# master-board_plus_slave.net
KiCad netlist of a schematic drawn in EAGLE
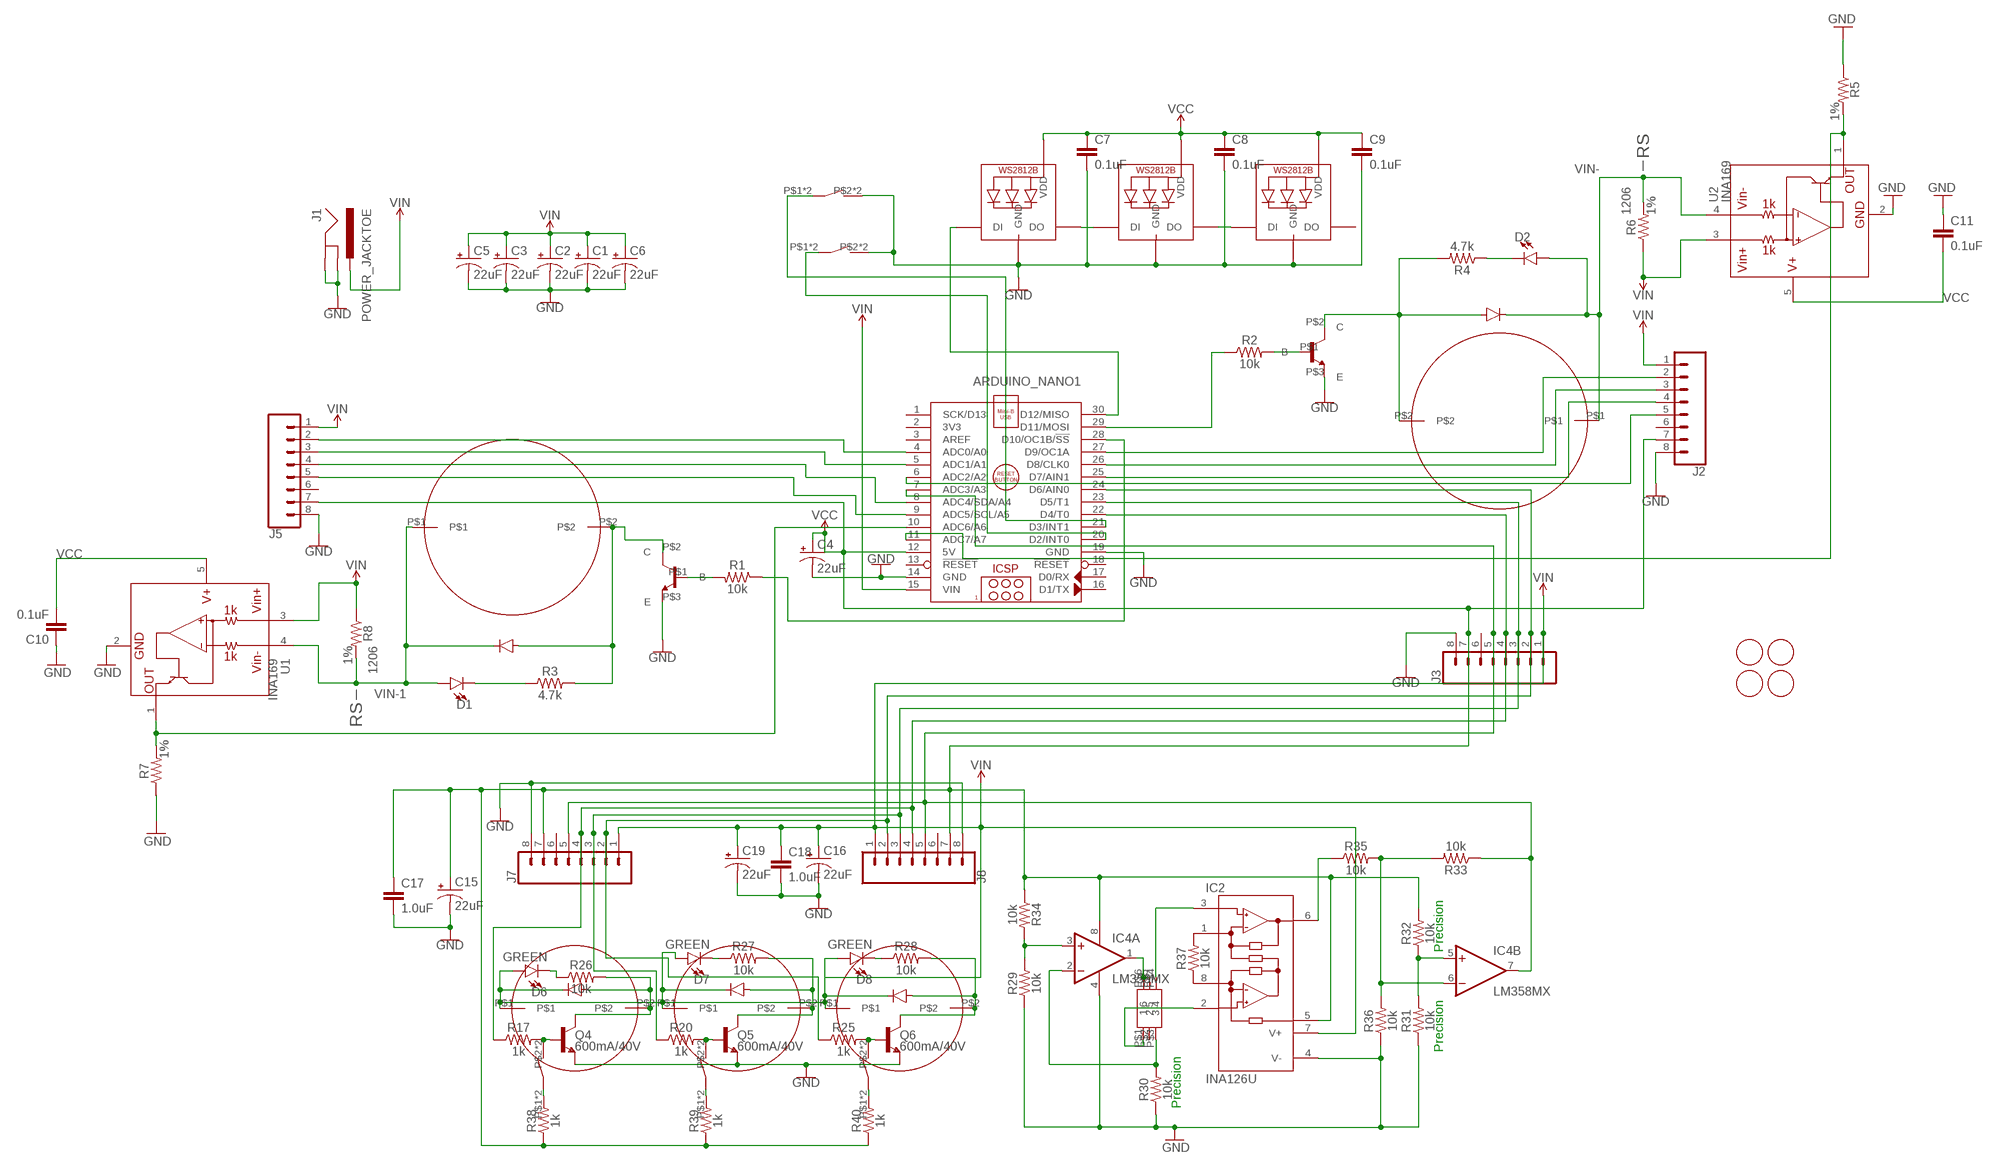
[diagram p0: schematic, sheet 1]

(export (version "E")
  (design (tool "Eeschema 10.0.6"))
  (components
    (comp (ref "ARDUINO_NANO1")
      (value "ARDUINO_NANO")
      (footprint "eagle-import:ARDUINO_NANO")
      (libsource (lib "eagle-import") (part "ARDUINO_NANO"))
    )
    (comp (ref "C1")
      (value "22uF")
      (footprint "eagle-import:PANASONIC_C")
      (libsource (lib "eagle-import") (part "22UF-POLAR-PANASONIC_C-35V-20%"))
    )
    (comp (ref "C2")
      (value "22uF")
      (footprint "eagle-import:PANASONIC_C")
      (libsource (lib "eagle-import") (part "22UF-POLAR-PANASONIC_C-35V-20%"))
    )
    (comp (ref "C3")
      (value "22uF")
      (footprint "eagle-import:PANASONIC_C")
      (libsource (lib "eagle-import") (part "22UF-POLAR-PANASONIC_C-35V-20%"))
    )
    (comp (ref "C4")
      (value "22uF")
      (footprint "eagle-import:PANASONIC_C")
      (libsource (lib "eagle-import") (part "22UF-POLAR-PANASONIC_C-35V-20%"))
    )
    (comp (ref "C5")
      (value "22uF")
      (footprint "eagle-import:PANASONIC_C")
      (libsource (lib "eagle-import") (part "22UF-POLAR-PANASONIC_C-35V-20%"))
    )
    (comp (ref "C6")
      (value "22uF")
      (footprint "eagle-import:PANASONIC_C")
      (libsource (lib "eagle-import") (part "22UF-POLAR-PANASONIC_C-35V-20%"))
    )
    (comp (ref "C7")
      (value "0.1uF")
      (footprint "eagle-import:0603")
      (libsource (lib "eagle-import") (part "0.1UF-0603-25V-(+80/-20%)"))
    )
    (comp (ref "C8")
      (value "0.1uF")
      (footprint "eagle-import:0603")
      (libsource (lib "eagle-import") (part "0.1UF-0603-25V-(+80/-20%)"))
    )
    (comp (ref "C9")
      (value "0.1uF")
      (footprint "eagle-import:0603")
      (libsource (lib "eagle-import") (part "0.1UF-0603-25V-(+80/-20%)"))
    )
    (comp (ref "C10")
      (value "0.1uF")
      (footprint "eagle-import:0603-CAP")
      (libsource (lib "eagle-import") (part "CAP0603-CAP"))
    )
    (comp (ref "C11")
      (value "0.1uF")
      (footprint "eagle-import:0603-CAP")
      (libsource (lib "eagle-import") (part "CAP0603-CAP"))
    )
    (comp (ref "C15")
      (value "22uF")
      (footprint "eagle-import:PANASONIC_C")
      (libsource (lib "eagle-import") (part "22UF-POLAR-PANASONIC_C-35V-20%"))
    )
    (comp (ref "C16")
      (value "22uF")
      (footprint "eagle-import:PANASONIC_C")
      (libsource (lib "eagle-import") (part "22UF-POLAR-PANASONIC_C-35V-20%"))
    )
    (comp (ref "C17")
      (value "1.0uF")
      (footprint "eagle-import:0603")
      (libsource (lib "eagle-import") (part "1.0UF-0603-16V-10%"))
    )
    (comp (ref "C18")
      (value "1.0uF")
      (footprint "eagle-import:0603")
      (libsource (lib "eagle-import") (part "1.0UF-0603-16V-10%"))
    )
    (comp (ref "C19")
      (value "22uF")
      (footprint "eagle-import:PANASONIC_C")
      (libsource (lib "eagle-import") (part "22UF-POLAR-PANASONIC_C-35V-20%"))
    )
    (comp (ref "D1")
      (value "LED0603")
      (footprint "eagle-import:LED-0603")
      (libsource (lib "eagle-import") (part "LED0603"))
    )
    (comp (ref "D2")
      (value "LED0603")
      (footprint "eagle-import:LED-0603")
      (libsource (lib "eagle-import") (part "LED0603"))
    )
    (comp (ref "D6")
      (value "GREEN")
      (footprint "eagle-import:LED-0603")
      (libsource (lib "eagle-import") (part "LED-GREEN0603"))
    )
    (comp (ref "D7")
      (value "GREEN")
      (footprint "eagle-import:LED-0603")
      (libsource (lib "eagle-import") (part "LED-GREEN0603"))
    )
    (comp (ref "D8")
      (value "GREEN")
      (footprint "eagle-import:LED-0603")
      (libsource (lib "eagle-import") (part "LED-GREEN0603"))
    )
    (comp (ref "IC2")
      (value "INA126U")
      (footprint "eagle-import:SO08")
      (fields (field (name "MF") "Texas Instruments") (field (name "MP") "INA126"))
      (libsource (lib "eagle-import") (part "INA126U"))
    )
    (comp (ref "IC4")
      (value "LM358MX")
      (footprint "eagle-import:SO08")
      (libsource (lib "eagle-import") (part "LM358MX"))
    )
    (comp (ref "J1")
      (value "POWER_JACKTOE")
      (footprint "eagle-import:POWER_JACK_SMD_OVERPASTE_TOE")
      (libsource (lib "eagle-import") (part "POWER_JACKTOE"))
    )
    (comp (ref "J2")
      (value "CONN_08\"")
      (footprint "eagle-import:1X08")
      (libsource (lib "eagle-import") (part "CONN_08{dblquote}"))
    )
    (comp (ref "J3")
      (value "CONN_08\"")
      (footprint "eagle-import:1X08")
      (libsource (lib "eagle-import") (part "CONN_08{dblquote}"))
    )
    (comp (ref "J5")
      (value "CONN_08\"")
      (footprint "eagle-import:1X08")
      (libsource (lib "eagle-import") (part "CONN_08{dblquote}"))
    )
    (comp (ref "J7")
      (value "CONN_08\"")
      (footprint "eagle-import:1X08")
      (libsource (lib "eagle-import") (part "CONN_08{dblquote}"))
    )
    (comp (ref "J8")
      (value "CONN_08\"")
      (footprint "eagle-import:1X08")
      (libsource (lib "eagle-import") (part "CONN_08{dblquote}"))
    )
    (comp (ref "LED1")
      (value "WS2812B5050")
      (footprint "eagle-import:WS2812B")
      (libsource (lib "eagle-import") (part "WS2812B5050"))
    )
    (comp (ref "LED2")
      (value "WS2812B5050")
      (footprint "eagle-import:WS2812B")
      (libsource (lib "eagle-import") (part "WS2812B5050"))
    )
    (comp (ref "LED3")
      (value "WS2812B5050")
      (footprint "eagle-import:WS2812B")
      (libsource (lib "eagle-import") (part "WS2812B5050"))
    )
    (comp (ref "Q4")
      (value "600mA/40V")
      (footprint "eagle-import:SOT23-3")
      (libsource (lib "eagle-import") (part "TRANS_NPN-MMBT2222AL"))
    )
    (comp (ref "Q5")
      (value "600mA/40V")
      (footprint "eagle-import:SOT23-3")
      (libsource (lib "eagle-import") (part "TRANS_NPN-MMBT2222AL"))
    )
    (comp (ref "Q6")
      (value "600mA/40V")
      (footprint "eagle-import:SOT23-3")
      (libsource (lib "eagle-import") (part "TRANS_NPN-MMBT2222AL"))
    )
    (comp (ref "R1")
      (value "10k")
      (footprint "eagle-import:0603")
      (libsource (lib "eagle-import") (part "10KOHM-0603-1/10W-1%"))
    )
    (comp (ref "R2")
      (value "10k")
      (footprint "eagle-import:0603")
      (libsource (lib "eagle-import") (part "10KOHM-0603-1/10W-1%"))
    )
    (comp (ref "R3")
      (value "4.7k")
      (footprint "eagle-import:0603")
      (libsource (lib "eagle-import") (part "4.7KOHM-0603-1/10W-1%"))
    )
    (comp (ref "R4")
      (value "4.7k")
      (footprint "eagle-import:0603")
      (libsource (lib "eagle-import") (part "4.7KOHM-0603-1/10W-1%"))
    )
    (comp (ref "R5")
      (value "RESISTOR0603")
      (footprint "eagle-import:0603")
      (fields (field (name "TOL") "1%"))
      (libsource (lib "eagle-import") (part "RESISTOR0603"))
    )
    (comp (ref "R6")
      (value "RESISTOR1206")
      (footprint "eagle-import:1206")
      (fields (field (name "SIZE") "1206") (field (name "TOL") "1%"))
      (libsource (lib "eagle-import") (part "RESISTOR1206"))
    )
    (comp (ref "R7")
      (value "RESISTOR0603")
      (footprint "eagle-import:0603")
      (fields (field (name "TOL") "1%"))
      (libsource (lib "eagle-import") (part "RESISTOR0603"))
    )
    (comp (ref "R8")
      (value "RESISTOR1206")
      (footprint "eagle-import:1206")
      (fields (field (name "SIZE") "1206") (field (name "TOL") "1%"))
      (libsource (lib "eagle-import") (part "RESISTOR1206"))
    )
    (comp (ref "R17")
      (value "1k")
      (footprint "eagle-import:0603")
      (libsource (lib "eagle-import") (part "1KOHM-0603-1/10W-1%"))
    )
    (comp (ref "R20")
      (value "1k")
      (footprint "eagle-import:0603")
      (libsource (lib "eagle-import") (part "1KOHM-0603-1/10W-1%"))
    )
    (comp (ref "R25")
      (value "1k")
      (footprint "eagle-import:0603")
      (libsource (lib "eagle-import") (part "1KOHM-0603-1/10W-1%"))
    )
    (comp (ref "R26")
      (value "10k")
      (footprint "eagle-import:0603")
      (libsource (lib "eagle-import") (part "10KOHM-0603-1/10W-1%"))
    )
    (comp (ref "R27")
      (value "10k")
      (footprint "eagle-import:0603")
      (libsource (lib "eagle-import") (part "10KOHM-0603-1/10W-1%"))
    )
    (comp (ref "R28")
      (value "10k")
      (footprint "eagle-import:0603")
      (libsource (lib "eagle-import") (part "10KOHM-0603-1/10W-1%"))
    )
    (comp (ref "R29")
      (value "10k")
      (footprint "eagle-import:0603")
      (libsource (lib "eagle-import") (part "10KOHM-0603-1/10W-1%"))
    )
    (comp (ref "R30")
      (value "10k")
      (footprint "eagle-import:0603")
      (libsource (lib "eagle-import") (part "10KOHM-0603-1/10W-1%"))
    )
    (comp (ref "R31")
      (value "10k")
      (footprint "eagle-import:0603")
      (libsource (lib "eagle-import") (part "10KOHM-0603-1/10W-1%"))
    )
    (comp (ref "R32")
      (value "10k")
      (footprint "eagle-import:0603")
      (libsource (lib "eagle-import") (part "10KOHM-0603-1/10W-1%"))
    )
    (comp (ref "R33")
      (value "10k")
      (footprint "eagle-import:0603")
      (libsource (lib "eagle-import") (part "10KOHM-0603-1/10W-1%"))
    )
    (comp (ref "R34")
      (value "10k")
      (footprint "eagle-import:0603")
      (libsource (lib "eagle-import") (part "10KOHM-0603-1/10W-1%"))
    )
    (comp (ref "R35")
      (value "10k")
      (footprint "eagle-import:0603")
      (libsource (lib "eagle-import") (part "10KOHM-0603-1/10W-1%"))
    )
    (comp (ref "R36")
      (value "10k")
      (footprint "eagle-import:0603")
      (libsource (lib "eagle-import") (part "10KOHM-0603-1/10W-1%"))
    )
    (comp (ref "R37")
      (value "10k")
      (footprint "eagle-import:0603")
      (libsource (lib "eagle-import") (part "10KOHM-0603-1/10W-1%"))
    )
    (comp (ref "R38")
      (value "1k")
      (footprint "eagle-import:0603")
      (libsource (lib "eagle-import") (part "1KOHM-0603-1/10W-1%"))
    )
    (comp (ref "R39")
      (value "1k")
      (footprint "eagle-import:0603")
      (libsource (lib "eagle-import") (part "1KOHM-0603-1/10W-1%"))
    )
    (comp (ref "R40")
      (value "1k")
      (footprint "eagle-import:0603")
      (libsource (lib "eagle-import") (part "1KOHM-0603-1/10W-1%"))
    )
    (comp (ref "U$1")
      (value "AIYIMA-PUMP-A5F083")
      (footprint "eagle-import:A5F083")
      (libsource (lib "eagle-import") (part "AIYIMA-PUMP-A5F083"))
    )
    (comp (ref "U$2")
      (value "AIYIMA-PUMP-A5F083")
      (footprint "eagle-import:A5F083")
      (libsource (lib "eagle-import") (part "AIYIMA-PUMP-A5F083"))
    )
    (comp (ref "U$3")
      (value "IN4148")
      (footprint "eagle-import:IN4148")
      (libsource (lib "eagle-import") (part "IN4148"))
    )
    (comp (ref "U$4")
      (value "IN4148")
      (footprint "eagle-import:IN4148")
      (libsource (lib "eagle-import") (part "IN4148"))
    )
    (comp (ref "U$5")
      (value "TIP120-TO220")
      (footprint "eagle-import:TO220")
      (libsource (lib "eagle-import") (part "TIP120-TO220"))
    )
    (comp (ref "U$6")
      (value "TIP120-TO220")
      (footprint "eagle-import:TO220")
      (libsource (lib "eagle-import") (part "TIP120-TO220"))
    )
    (comp (ref "U$7")
      (value "BUTTON")
      (footprint "eagle-import:BUTTON")
      (libsource (lib "eagle-import") (part "BUTTON"))
    )
    (comp (ref "U$8")
      (value "BUTTON")
      (footprint "eagle-import:BUTTON")
      (libsource (lib "eagle-import") (part "BUTTON"))
    )
    (comp (ref "U$9")
      (value "FIDUCIAL")
      (footprint "eagle-import:FIDUCIAL_1MM")
      (libsource (lib "eagle-import") (part "FIDUCIAL"))
    )
    (comp (ref "U$10")
      (value "FIDUCIAL")
      (footprint "eagle-import:FIDUCIAL_1MM")
      (libsource (lib "eagle-import") (part "FIDUCIAL"))
    )
    (comp (ref "U$11")
      (value "FIDUCIAL")
      (footprint "eagle-import:FIDUCIAL_1MM")
      (libsource (lib "eagle-import") (part "FIDUCIAL"))
    )
    (comp (ref "U$12")
      (value "FIDUCIAL")
      (footprint "eagle-import:FIDUCIAL_1MM")
      (libsource (lib "eagle-import") (part "FIDUCIAL"))
    )
    (comp (ref "U$17")
      (value "CJV23-SOLENOID-VALVE")
      (footprint "eagle-import:CJV23")
      (libsource (lib "eagle-import") (part "CJV23-SOLENOID-VALVE"))
    )
    (comp (ref "U$18")
      (value "CJV23-SOLENOID-VALVE")
      (footprint "eagle-import:CJV23")
      (libsource (lib "eagle-import") (part "CJV23-SOLENOID-VALVE"))
    )
    (comp (ref "U$19")
      (value "CJV23-SOLENOID-VALVE")
      (footprint "eagle-import:CJV23")
      (libsource (lib "eagle-import") (part "CJV23-SOLENOID-VALVE"))
    )
    (comp (ref "U$20")
      (value "IN4148")
      (footprint "eagle-import:IN4148")
      (libsource (lib "eagle-import") (part "IN4148"))
    )
    (comp (ref "U$21")
      (value "IN4148")
      (footprint "eagle-import:IN4148")
      (libsource (lib "eagle-import") (part "IN4148"))
    )
    (comp (ref "U$22")
      (value "IN4148")
      (footprint "eagle-import:IN4148")
      (libsource (lib "eagle-import") (part "IN4148"))
    )
    (comp (ref "U$23")
      (value "2SMPP-03")
      (footprint "eagle-import:2SMPP-03")
      (libsource (lib "eagle-import") (part "2SMPP-03"))
    )
    (comp (ref "U$24")
      (value "BUTTON")
      (footprint "eagle-import:BUTTON")
      (libsource (lib "eagle-import") (part "BUTTON"))
    )
    (comp (ref "U$25")
      (value "BUTTON")
      (footprint "eagle-import:BUTTON")
      (libsource (lib "eagle-import") (part "BUTTON"))
    )
    (comp (ref "U$26")
      (value "BUTTON")
      (footprint "eagle-import:BUTTON")
      (libsource (lib "eagle-import") (part "BUTTON"))
    )
    (comp (ref "U1")
      (value "INA169")
      (footprint "eagle-import:SOT23-5")
      (libsource (lib "eagle-import") (part "INA169"))
    )
    (comp (ref "U2")
      (value "INA169")
      (footprint "eagle-import:SOT23-5")
      (libsource (lib "eagle-import") (part "INA169"))
    )
  )
  (nets
    (net (code "1") (name "/VIN-") (class "Default")
      (node (ref "D2") (pin "A") (pinfunction "A_A") (pintype "passive"))
      (node (ref "R6") (pin "2") (pinfunction "2_2") (pintype "passive"))
      (node (ref "U$2") (pin "P$1") (pinfunction "P$1_P$1") (pintype "bidirectional"))
      (node (ref "U$4") (pin "P$1") (pinfunction "P$1_P$1") (pintype "bidirectional"))
      (node (ref "U2") (pin "4") (pinfunction "VIN-_4") (pintype "bidirectional"))
    )
    (net (code "2") (name "/VIN-1") (class "Default")
      (node (ref "D1") (pin "A") (pinfunction "A_A") (pintype "passive"))
      (node (ref "R8") (pin "2") (pinfunction "2_2") (pintype "passive"))
      (node (ref "U$1") (pin "P$1") (pinfunction "P$1_P$1") (pintype "bidirectional"))
      (node (ref "U$3") (pin "P$1") (pinfunction "P$1_P$1") (pintype "bidirectional"))
      (node (ref "U1") (pin "4") (pinfunction "VIN-_4") (pintype "bidirectional"))
    )
    (net (code "3") (name "GND") (class "Default")
      (node (ref "ARDUINO_NANO1") (pin "14") (pinfunction "GND_14") (pintype "power_in"))
      (node (ref "ARDUINO_NANO1") (pin "19") (pinfunction "GND_19") (pintype "power_in"))
      (node (ref "C1") (pin "-") (pinfunction "-_-") (pintype "passive"))
      (node (ref "C10") (pin "1") (pinfunction "1_1") (pintype "passive"))
      (node (ref "C11") (pin "1") (pinfunction "1_1") (pintype "passive"))
      (node (ref "C15") (pin "-") (pinfunction "-_-") (pintype "passive"))
      (node (ref "C16") (pin "-") (pinfunction "-_-") (pintype "passive"))
      (node (ref "C17") (pin "2") (pinfunction "2_2") (pintype "passive"))
      (node (ref "C18") (pin "2") (pinfunction "2_2") (pintype "passive"))
      (node (ref "C19") (pin "-") (pinfunction "-_-") (pintype "passive"))
      (node (ref "C2") (pin "-") (pinfunction "-_-") (pintype "passive"))
      (node (ref "C3") (pin "-") (pinfunction "-_-") (pintype "passive"))
      (node (ref "C4") (pin "-") (pinfunction "-_-") (pintype "passive"))
      (node (ref "C5") (pin "-") (pinfunction "-_-") (pintype "passive"))
      (node (ref "C6") (pin "-") (pinfunction "-_-") (pintype "passive"))
      (node (ref "C7") (pin "2") (pinfunction "2_2") (pintype "passive"))
      (node (ref "C8") (pin "2") (pinfunction "2_2") (pintype "passive"))
      (node (ref "C9") (pin "2") (pinfunction "2_2") (pintype "passive"))
      (node (ref "IC2") (pin "4") (pinfunction "V-_4") (pintype "power_in"))
      (node (ref "IC4") (pin "4") (pinfunction "V-_4") (pintype "power_in"))
      (node (ref "J1") (pin "GND") (pinfunction "GNDBREAK_GND") (pintype "bidirectional"))
      (node (ref "J1") (pin "P$4") (pinfunction "GND_P$4") (pintype "bidirectional"))
      (node (ref "J2") (pin "8") (pinfunction "8_8") (pintype "passive"))
      (node (ref "J3") (pin "8") (pinfunction "8_8") (pintype "passive"))
      (node (ref "J5") (pin "8") (pinfunction "8_8") (pintype "passive"))
      (node (ref "J7") (pin "8") (pinfunction "8_8") (pintype "passive"))
      (node (ref "J8") (pin "8") (pinfunction "8_8") (pintype "passive"))
      (node (ref "LED1") (pin "3-GND") (pinfunction "GND_3-GND") (pintype "power_in"))
      (node (ref "LED2") (pin "3-GND") (pinfunction "GND_3-GND") (pintype "power_in"))
      (node (ref "LED3") (pin "3-GND") (pinfunction "GND_3-GND") (pintype "power_in"))
      (node (ref "Q4") (pin "2") (pinfunction "E_2") (pintype "passive"))
      (node (ref "Q5") (pin "2") (pinfunction "E_2") (pintype "passive"))
      (node (ref "Q6") (pin "2") (pinfunction "E_2") (pintype "passive"))
      (node (ref "R29") (pin "1") (pinfunction "1_1") (pintype "passive"))
      (node (ref "R30") (pin "1") (pinfunction "1_1") (pintype "passive"))
      (node (ref "R31") (pin "1") (pinfunction "1_1") (pintype "passive"))
      (node (ref "R36") (pin "1") (pinfunction "1_1") (pintype "passive"))
      (node (ref "R5") (pin "1") (pinfunction "1_1") (pintype "passive"))
      (node (ref "R7") (pin "1") (pinfunction "1_1") (pintype "passive"))
      (node (ref "U$5") (pin "P$3") (pinfunction "E_P$3") (pintype "bidirectional"))
      (node (ref "U$6") (pin "P$3") (pinfunction "E_P$3") (pintype "bidirectional"))
      (node (ref "U$7") (pin "P$2") (pinfunction "P$2_P$2") (pintype "bidirectional"))
      (node (ref "U$7") (pin "P$4") (pinfunction "P$2_P$4") (pintype "bidirectional"))
      (node (ref "U$8") (pin "P$2") (pinfunction "P$2_P$2") (pintype "bidirectional"))
      (node (ref "U$8") (pin "P$4") (pinfunction "P$2_P$4") (pintype "bidirectional"))
      (node (ref "U1") (pin "2") (pinfunction "GND_2") (pintype "bidirectional"))
      (node (ref "U2") (pin "2") (pinfunction "GND_2") (pintype "bidirectional"))
    )
    (net (code "4") (name "Net-(ARDUINO_NANO1-ADC0{slash}A0)") (class "Default")
      (node (ref "ARDUINO_NANO1") (pin "4") (pinfunction "ADC0/A0_4") (pintype "bidirectional"))
      (node (ref "J5") (pin "2") (pinfunction "2_2") (pintype "passive"))
    )
    (net (code "5") (name "Net-(ARDUINO_NANO1-ADC1{slash}A1)") (class "Default")
      (node (ref "ARDUINO_NANO1") (pin "5") (pinfunction "ADC1/A1_5") (pintype "bidirectional"))
      (node (ref "J5") (pin "3") (pinfunction "3_3") (pintype "passive"))
    )
    (net (code "6") (name "Net-(ARDUINO_NANO1-ADC2{slash}A2)") (class "Default")
      (node (ref "ARDUINO_NANO1") (pin "6") (pinfunction "ADC2/A2_6") (pintype "bidirectional"))
      (node (ref "J2") (pin "5") (pinfunction "5_5") (pintype "passive"))
    )
    (net (code "7") (name "Net-(ARDUINO_NANO1-ADC3{slash}A3)") (class "Default")
      (node (ref "ARDUINO_NANO1") (pin "7") (pinfunction "ADC3/A3_7") (pintype "bidirectional"))
      (node (ref "IC4") (pin "7") (pinfunction "OUT_7") (pintype "output"))
      (node (ref "J3") (pin "5") (pinfunction "5_5") (pintype "passive"))
      (node (ref "J7") (pin "5") (pinfunction "5_5") (pintype "passive"))
      (node (ref "J8") (pin "5") (pinfunction "5_5") (pintype "passive"))
      (node (ref "R33") (pin "1") (pinfunction "1_1") (pintype "passive"))
    )
    (net (code "8") (name "Net-(ARDUINO_NANO1-ADC4{slash}SDA{slash}A4)") (class "Default")
      (node (ref "ARDUINO_NANO1") (pin "8") (pinfunction "ADC4/SDA/A4_8") (pintype "bidirectional"))
      (node (ref "J5") (pin "4") (pinfunction "4_4") (pintype "passive"))
    )
    (net (code "9") (name "Net-(ARDUINO_NANO1-ADC5{slash}SCL{slash}A5)") (class "Default")
      (node (ref "ARDUINO_NANO1") (pin "9") (pinfunction "ADC5/SCL/A5_9") (pintype "bidirectional"))
      (node (ref "J5") (pin "5") (pinfunction "5_5") (pintype "passive"))
    )
    (net (code "10") (name "Net-(ARDUINO_NANO1-ADC6{slash}A6)") (class "Default")
      (node (ref "ARDUINO_NANO1") (pin "10") (pinfunction "ADC6/A6_10") (pintype "bidirectional"))
      (node (ref "R7") (pin "2") (pinfunction "2_2") (pintype "passive"))
      (node (ref "U1") (pin "1") (pinfunction "OUT_1") (pintype "bidirectional"))
    )
    (net (code "11") (name "Net-(ARDUINO_NANO1-ADC7{slash}A7)") (class "Default")
      (node (ref "ARDUINO_NANO1") (pin "11") (pinfunction "ADC7/A7_11") (pintype "bidirectional"))
      (node (ref "R5") (pin "2") (pinfunction "2_2") (pintype "passive"))
      (node (ref "U2") (pin "1") (pinfunction "OUT_1") (pintype "bidirectional"))
    )
    (net (code "12") (name "Net-(ARDUINO_NANO1-D2{slash}INT0)") (class "Default")
      (node (ref "ARDUINO_NANO1") (pin "20") (pinfunction "D2/INT0_20") (pintype "bidirectional"))
      (node (ref "U$8") (pin "P$1") (pinfunction "P$1_P$1") (pintype "bidirectional"))
      (node (ref "U$8") (pin "P$3") (pinfunction "P$1_P$3") (pintype "bidirectional"))
    )
    (net (code "13") (name "Net-(ARDUINO_NANO1-D3{slash}INT1)") (class "Default")
      (node (ref "ARDUINO_NANO1") (pin "21") (pinfunction "D3/INT1_21") (pintype "bidirectional"))
      (node (ref "U$7") (pin "P$1") (pinfunction "P$1_P$1") (pintype "bidirectional"))
      (node (ref "U$7") (pin "P$3") (pinfunction "P$1_P$3") (pintype "bidirectional"))
    )
    (net (code "14") (name "Net-(ARDUINO_NANO1-D4{slash}T0)") (class "Default")
      (node (ref "ARDUINO_NANO1") (pin "22") (pinfunction "D4/T0_22") (pintype "bidirectional"))
      (node (ref "J3") (pin "4") (pinfunction "4_4") (pintype "passive"))
      (node (ref "J7") (pin "4") (pinfunction "4_4") (pintype "passive"))
      (node (ref "J8") (pin "4") (pinfunction "4_4") (pintype "passive"))
      (node (ref "R17") (pin "1") (pinfunction "1_1") (pintype "passive"))
    )
    (net (code "15") (name "Net-(ARDUINO_NANO1-D5{slash}T1)") (class "Default")
      (node (ref "ARDUINO_NANO1") (pin "23") (pinfunction "D5/T1_23") (pintype "bidirectional"))
      (node (ref "J3") (pin "3") (pinfunction "3_3") (pintype "passive"))
      (node (ref "J7") (pin "3") (pinfunction "3_3") (pintype "passive"))
      (node (ref "J8") (pin "3") (pinfunction "3_3") (pintype "passive"))
      (node (ref "R20") (pin "1") (pinfunction "1_1") (pintype "passive"))
    )
    (net (code "16") (name "Net-(ARDUINO_NANO1-D6{slash}AIN0)") (class "Default")
      (node (ref "ARDUINO_NANO1") (pin "24") (pinfunction "D6/AIN0_24") (pintype "bidirectional"))
      (node (ref "J3") (pin "2") (pinfunction "2_2") (pintype "passive"))
      (node (ref "J7") (pin "2") (pinfunction "2_2") (pintype "passive"))
      (node (ref "J8") (pin "2") (pinfunction "2_2") (pintype "passive"))
      (node (ref "R25") (pin "1") (pinfunction "1_1") (pintype "passive"))
    )
    (net (code "17") (name "Net-(ARDUINO_NANO1-D7{slash}AIN1)") (class "Default")
      (node (ref "ARDUINO_NANO1") (pin "25") (pinfunction "D7/AIN1_25") (pintype "bidirectional"))
      (node (ref "J2") (pin "4") (pinfunction "4_4") (pintype "passive"))
    )
    (net (code "18") (name "Net-(ARDUINO_NANO1-D8{slash}CLK0)") (class "Default")
      (node (ref "ARDUINO_NANO1") (pin "26") (pinfunction "D8/CLK0_26") (pintype "bidirectional"))
      (node (ref "J2") (pin "3") (pinfunction "3_3") (pintype "passive"))
    )
    (net (code "19") (name "Net-(ARDUINO_NANO1-D9{slash}OC1A)") (class "Default")
      (node (ref "ARDUINO_NANO1") (pin "27") (pinfunction "D9/OC1A_27") (pintype "bidirectional"))
      (node (ref "J2") (pin "2") (pinfunction "2_2") (pintype "passive"))
    )
    (net (code "20") (name "Net-(ARDUINO_NANO1-D10{slash}OC1B{slash}~{SS})") (class "Default")
      (node (ref "ARDUINO_NANO1") (pin "28") (pinfunction "D10/OC1B/~{SS}_28") (pintype "bidirectional"))
      (node (ref "R1") (pin "1") (pinfunction "1_1") (pintype "passive"))
    )
    (net (code "21") (name "Net-(ARDUINO_NANO1-D11{slash}MOSI)") (class "Default")
      (node (ref "ARDUINO_NANO1") (pin "29") (pinfunction "D11/MOSI_29") (pintype "bidirectional"))
      (node (ref "R2") (pin "1") (pinfunction "1_1") (pintype "passive"))
    )
    (net (code "22") (name "Net-(ARDUINO_NANO1-D12{slash}MISO)") (class "Default")
      (node (ref "ARDUINO_NANO1") (pin "30") (pinfunction "D12/MISO_30") (pintype "bidirectional"))
      (node (ref "LED1") (pin "4-DIN") (pinfunction "DI_4-DIN") (pintype "input"))
    )
    (net (code "23") (name "Net-(D1-PadC)") (class "Default")
      (node (ref "D1") (pin "C") (pinfunction "C_C") (pintype "passive"))
      (node (ref "R3") (pin "1") (pinfunction "1_1") (pintype "passive"))
    )
    (net (code "24") (name "Net-(D2-PadC)") (class "Default")
      (node (ref "D2") (pin "C") (pinfunction "C_C") (pintype "passive"))
      (node (ref "R4") (pin "1") (pinfunction "1_1") (pintype "passive"))
    )
    (net (code "25") (name "Net-(D6-PadC)") (class "Default")
      (node (ref "D6") (pin "C") (pinfunction "C_C") (pintype "passive"))
      (node (ref "R26") (pin "1") (pinfunction "1_1") (pintype "passive"))
    )
    (net (code "26") (name "Net-(D7-PadC)") (class "Default")
      (node (ref "D7") (pin "C") (pinfunction "C_C") (pintype "passive"))
      (node (ref "R27") (pin "1") (pinfunction "1_1") (pintype "passive"))
    )
    (net (code "27") (name "Net-(D8-PadC)") (class "Default")
      (node (ref "D8") (pin "C") (pinfunction "C_C") (pintype "passive"))
      (node (ref "R28") (pin "1") (pinfunction "1_1") (pintype "passive"))
    )
    (net (code "28") (name "Net-(IC2-+IN)") (class "Default")
      (node (ref "IC2") (pin "3") (pinfunction "+IN_3") (pintype "input"))
      (node (ref "U$23") (pin "P$4") (pinfunction "4_P$4") (pintype "bidirectional"))
    )
    (net (code "29") (name "Net-(IC2--IN)") (class "Default")
      (node (ref "IC2") (pin "2") (pinfunction "-IN_2") (pintype "input"))
      (node (ref "U$23") (pin "P$1") (pinfunction "1_P$1") (pintype "bidirectional"))
    )
    (net (code "30") (name "Net-(IC2-OUT)") (class "Default")
      (node (ref "IC2") (pin "6") (pinfunction "OUT_6") (pintype "output"))
      (node (ref "R35") (pin "1") (pinfunction "1_1") (pintype "passive"))
    )
    (net (code "31") (name "Net-(IC2-RG-Pad1)") (class "Default")
      (node (ref "IC2") (pin "1") (pinfunction "RG_1") (pintype "passive"))
      (node (ref "R37") (pin "2") (pinfunction "2_2") (pintype "passive"))
    )
    (net (code "32") (name "Net-(IC2-RG-Pad8)") (class "Default")
      (node (ref "IC2") (pin "8") (pinfunction "RG_8") (pintype "passive"))
      (node (ref "R37") (pin "1") (pinfunction "1_1") (pintype "passive"))
    )
    (net (code "33") (name "Net-(IC4A-+IN)") (class "Default")
      (node (ref "IC4") (pin "3") (pinfunction "+IN_3") (pintype "input"))
      (node (ref "R29") (pin "2") (pinfunction "2_2") (pintype "passive"))
      (node (ref "R34") (pin "2") (pinfunction "2_2") (pintype "passive"))
    )
    (net (code "34") (name "Net-(IC4A--IN)") (class "Default")
      (node (ref "IC4") (pin "2") (pinfunction "-IN_2") (pintype "input"))
      (node (ref "R30") (pin "2") (pinfunction "2_2") (pintype "passive"))
      (node (ref "U$23") (pin "P$3") (pinfunction "3_P$3") (pintype "bidirectional"))
    )
    (net (code "35") (name "Net-(IC4A-OUT)") (class "Default")
      (node (ref "IC4") (pin "1") (pinfunction "OUT_1") (pintype "output"))
      (node (ref "U$23") (pin "P$5") (pinfunction "5_P$5") (pintype "bidirectional"))
      (node (ref "U$23") (pin "P$6") (pinfunction "6_P$6") (pintype "bidirectional"))
    )
    (net (code "36") (name "Net-(IC4B-+IN)") (class "Default")
      (node (ref "IC4") (pin "5") (pinfunction "+IN_5") (pintype "input"))
      (node (ref "R31") (pin "2") (pinfunction "2_2") (pintype "passive"))
      (node (ref "R32") (pin "1") (pinfunction "1_1") (pintype "passive"))
    )
    (net (code "37") (name "Net-(IC4B--IN)") (class "Default")
      (node (ref "IC4") (pin "6") (pinfunction "-IN_6") (pintype "input"))
      (node (ref "R33") (pin "2") (pinfunction "2_2") (pintype "passive"))
      (node (ref "R35") (pin "2") (pinfunction "2_2") (pintype "passive"))
      (node (ref "R36") (pin "2") (pinfunction "2_2") (pintype "passive"))
    )
    (net (code "38") (name "Net-(LED1-DO)") (class "Default")
      (node (ref "LED1") (pin "2-DOUT") (pinfunction "DO_2-DOUT") (pintype "output"))
      (node (ref "LED2") (pin "4-DIN") (pinfunction "DI_4-DIN") (pintype "input"))
    )
    (net (code "39") (name "Net-(LED2-DO)") (class "Default")
      (node (ref "LED2") (pin "2-DOUT") (pinfunction "DO_2-DOUT") (pintype "output"))
      (node (ref "LED3") (pin "4-DIN") (pinfunction "DI_4-DIN") (pintype "input"))
    )
    (net (code "40") (name "Net-(Q4-B)") (class "Default")
      (node (ref "Q4") (pin "1") (pinfunction "B_1") (pintype "passive"))
      (node (ref "R17") (pin "2") (pinfunction "2_2") (pintype "passive"))
      (node (ref "U$24") (pin "P$2") (pinfunction "P$2_P$2") (pintype "bidirectional"))
      (node (ref "U$24") (pin "P$4") (pinfunction "P$2_P$4") (pintype "bidirectional"))
    )
    (net (code "41") (name "Net-(Q4-C)") (class "Default")
      (node (ref "Q4") (pin "3") (pinfunction "C_3") (pintype "passive"))
      (node (ref "R26") (pin "2") (pinfunction "2_2") (pintype "passive"))
      (node (ref "U$17") (pin "P$2") (pinfunction "P$2_P$2") (pintype "bidirectional"))
      (node (ref "U$20") (pin "P$2") (pinfunction "P$2_P$2") (pintype "bidirectional"))
    )
    (net (code "42") (name "Net-(Q5-B)") (class "Default")
      (node (ref "Q5") (pin "1") (pinfunction "B_1") (pintype "passive"))
      (node (ref "R20") (pin "2") (pinfunction "2_2") (pintype "passive"))
      (node (ref "U$25") (pin "P$2") (pinfunction "P$2_P$2") (pintype "bidirectional"))
      (node (ref "U$25") (pin "P$4") (pinfunction "P$2_P$4") (pintype "bidirectional"))
    )
    (net (code "43") (name "Net-(Q5-C)") (class "Default")
      (node (ref "Q5") (pin "3") (pinfunction "C_3") (pintype "passive"))
      (node (ref "R27") (pin "2") (pinfunction "2_2") (pintype "passive"))
      (node (ref "U$18") (pin "P$2") (pinfunction "P$2_P$2") (pintype "bidirectional"))
      (node (ref "U$21") (pin "P$2") (pinfunction "P$2_P$2") (pintype "bidirectional"))
    )
    (net (code "44") (name "Net-(Q6-B)") (class "Default")
      (node (ref "Q6") (pin "1") (pinfunction "B_1") (pintype "passive"))
      (node (ref "R25") (pin "2") (pinfunction "2_2") (pintype "passive"))
      (node (ref "U$26") (pin "P$2") (pinfunction "P$2_P$2") (pintype "bidirectional"))
      (node (ref "U$26") (pin "P$4") (pinfunction "P$2_P$4") (pintype "bidirectional"))
    )
    (net (code "45") (name "Net-(Q6-C)") (class "Default")
      (node (ref "Q6") (pin "3") (pinfunction "C_3") (pintype "passive"))
      (node (ref "R28") (pin "2") (pinfunction "2_2") (pintype "passive"))
      (node (ref "U$19") (pin "P$2") (pinfunction "P$2_P$2") (pintype "bidirectional"))
      (node (ref "U$22") (pin "P$2") (pinfunction "P$2_P$2") (pintype "bidirectional"))
    )
    (net (code "46") (name "Net-(R38-Pad2)") (class "Default")
      (node (ref "R38") (pin "2") (pinfunction "2_2") (pintype "passive"))
      (node (ref "U$24") (pin "P$1") (pinfunction "P$1_P$1") (pintype "bidirectional"))
      (node (ref "U$24") (pin "P$3") (pinfunction "P$1_P$3") (pintype "bidirectional"))
    )
    (net (code "47") (name "Net-(R39-Pad2)") (class "Default")
      (node (ref "R39") (pin "2") (pinfunction "2_2") (pintype "passive"))
      (node (ref "U$25") (pin "P$1") (pinfunction "P$1_P$1") (pintype "bidirectional"))
      (node (ref "U$25") (pin "P$3") (pinfunction "P$1_P$3") (pintype "bidirectional"))
    )
    (net (code "48") (name "Net-(R40-Pad2)") (class "Default")
      (node (ref "R40") (pin "2") (pinfunction "2_2") (pintype "passive"))
      (node (ref "U$26") (pin "P$1") (pinfunction "P$1_P$1") (pintype "bidirectional"))
      (node (ref "U$26") (pin "P$3") (pinfunction "P$1_P$3") (pintype "bidirectional"))
    )
    (net (code "49") (name "Net-(U$5-B)") (class "Default")
      (node (ref "R2") (pin "2") (pinfunction "2_2") (pintype "passive"))
      (node (ref "U$5") (pin "P$1") (pinfunction "B_P$1") (pintype "bidirectional"))
    )
    (net (code "50") (name "Net-(U$5-C)") (class "Default")
      (node (ref "R4") (pin "2") (pinfunction "2_2") (pintype "passive"))
      (node (ref "U$2") (pin "P$2") (pinfunction "P$2_P$2") (pintype "bidirectional"))
      (node (ref "U$4") (pin "P$2") (pinfunction "P$2_P$2") (pintype "bidirectional"))
      (node (ref "U$5") (pin "P$2") (pinfunction "C_P$2") (pintype "bidirectional"))
    )
    (net (code "51") (name "Net-(U$6-B)") (class "Default")
      (node (ref "R1") (pin "2") (pinfunction "2_2") (pintype "passive"))
      (node (ref "U$6") (pin "P$1") (pinfunction "B_P$1") (pintype "bidirectional"))
    )
    (net (code "52") (name "Net-(U$6-C)") (class "Default")
      (node (ref "R3") (pin "2") (pinfunction "2_2") (pintype "passive"))
      (node (ref "U$1") (pin "P$2") (pinfunction "P$2_P$2") (pintype "bidirectional"))
      (node (ref "U$3") (pin "P$2") (pinfunction "P$2_P$2") (pintype "bidirectional"))
      (node (ref "U$6") (pin "P$2") (pinfunction "C_P$2") (pintype "bidirectional"))
    )
    (net (code "53") (name "VCC") (class "Default")
      (node (ref "ARDUINO_NANO1") (pin "12") (pinfunction "5V_12") (pintype "power_in"))
      (node (ref "C10") (pin "2") (pinfunction "2_2") (pintype "passive"))
      (node (ref "C11") (pin "2") (pinfunction "2_2") (pintype "passive"))
      (node (ref "C15") (pin "+") (pinfunction "+_+") (pintype "passive"))
      (node (ref "C17") (pin "1") (pinfunction "1_1") (pintype "passive"))
      (node (ref "C4") (pin "+") (pinfunction "+_+") (pintype "passive"))
      (node (ref "C7") (pin "1") (pinfunction "1_1") (pintype "passive"))
      (node (ref "C8") (pin "1") (pinfunction "1_1") (pintype "passive"))
      (node (ref "C9") (pin "1") (pinfunction "1_1") (pintype "passive"))
      (node (ref "IC2") (pin "5") (pinfunction "REF_5") (pintype "passive"))
      (node (ref "IC4") (pin "8") (pinfunction "V+_8") (pintype "power_in"))
      (node (ref "J2") (pin "7") (pinfunction "7_7") (pintype "passive"))
      (node (ref "J3") (pin "7") (pinfunction "7_7") (pintype "passive"))
      (node (ref "J5") (pin "7") (pinfunction "7_7") (pintype "passive"))
      (node (ref "J7") (pin "7") (pinfunction "7_7") (pintype "passive"))
      (node (ref "J8") (pin "7") (pinfunction "7_7") (pintype "passive"))
      (node (ref "LED1") (pin "1-VDD") (pinfunction "VDD_1-VDD") (pintype "power_in"))
      (node (ref "LED2") (pin "1-VDD") (pinfunction "VDD_1-VDD") (pintype "power_in"))
      (node (ref "LED3") (pin "1-VDD") (pinfunction "VDD_1-VDD") (pintype "power_in"))
      (node (ref "R32") (pin "2") (pinfunction "2_2") (pintype "passive"))
      (node (ref "R34") (pin "1") (pinfunction "1_1") (pintype "passive"))
      (node (ref "R38") (pin "1") (pinfunction "1_1") (pintype "passive"))
      (node (ref "R39") (pin "1") (pinfunction "1_1") (pintype "passive"))
      (node (ref "R40") (pin "1") (pinfunction "1_1") (pintype "passive"))
      (node (ref "U1") (pin "5") (pinfunction "V+_5") (pintype "bidirectional"))
      (node (ref "U2") (pin "5") (pinfunction "V+_5") (pintype "bidirectional"))
    )
    (net (code "54") (name "VIN") (class "Default")
      (node (ref "ARDUINO_NANO1") (pin "15") (pinfunction "VIN_15") (pintype "power_in"))
      (node (ref "C1") (pin "+") (pinfunction "+_+") (pintype "passive"))
      (node (ref "C16") (pin "+") (pinfunction "+_+") (pintype "passive"))
      (node (ref "C18") (pin "1") (pinfunction "1_1") (pintype "passive"))
      (node (ref "C19") (pin "+") (pinfunction "+_+") (pintype "passive"))
      (node (ref "C2") (pin "+") (pinfunction "+_+") (pintype "passive"))
      (node (ref "C3") (pin "+") (pinfunction "+_+") (pintype "passive"))
      (node (ref "C5") (pin "+") (pinfunction "+_+") (pintype "passive"))
      (node (ref "C6") (pin "+") (pinfunction "+_+") (pintype "passive"))
      (node (ref "D6") (pin "A") (pinfunction "A_A") (pintype "passive"))
      (node (ref "D7") (pin "A") (pinfunction "A_A") (pintype "passive"))
      (node (ref "D8") (pin "A") (pinfunction "A_A") (pintype "passive"))
      (node (ref "IC2") (pin "7") (pinfunction "V+_7") (pintype "power_in"))
      (node (ref "J1") (pin "VIN0") (pinfunction "PWR_VIN0") (pintype "bidirectional"))
      (node (ref "J2") (pin "1") (pinfunction "1_1") (pintype "passive"))
      (node (ref "J3") (pin "1") (pinfunction "1_1") (pintype "passive"))
      (node (ref "J5") (pin "1") (pinfunction "1_1") (pintype "passive"))
      (node (ref "J7") (pin "1") (pinfunction "1_1") (pintype "passive"))
      (node (ref "J8") (pin "1") (pinfunction "1_1") (pintype "passive"))
      (node (ref "R6") (pin "1") (pinfunction "1_1") (pintype "passive"))
      (node (ref "R8") (pin "1") (pinfunction "1_1") (pintype "passive"))
      (node (ref "U$17") (pin "P$1") (pinfunction "P$1_P$1") (pintype "bidirectional"))
      (node (ref "U$18") (pin "P$1") (pinfunction "P$1_P$1") (pintype "bidirectional"))
      (node (ref "U$19") (pin "P$1") (pinfunction "P$1_P$1") (pintype "bidirectional"))
      (node (ref "U$20") (pin "P$1") (pinfunction "P$1_P$1") (pintype "bidirectional"))
      (node (ref "U$21") (pin "P$1") (pinfunction "P$1_P$1") (pintype "bidirectional"))
      (node (ref "U$22") (pin "P$1") (pinfunction "P$1_P$1") (pintype "bidirectional"))
      (node (ref "U1") (pin "3") (pinfunction "VIN+_3") (pintype "bidirectional"))
      (node (ref "U2") (pin "3") (pinfunction "VIN+_3") (pintype "bidirectional"))
    )
    (net (code "55") (name "unconnected-(ARDUINO_NANO1-3V3-Pad2)") (class "Default")
      (node (ref "ARDUINO_NANO1") (pin "2") (pinfunction "3V3_2") (pintype "output"))
    )
    (net (code "56") (name "unconnected-(ARDUINO_NANO1-AREF-Pad3)") (class "Default")
      (node (ref "ARDUINO_NANO1") (pin "3") (pinfunction "AREF_3") (pintype "input"))
    )
    (net (code "57") (name "unconnected-(ARDUINO_NANO1-D0{slash}RX-Pad17)") (class "Default")
      (node (ref "ARDUINO_NANO1") (pin "17") (pinfunction "D0/RX_17") (pintype "bidirectional"))
    )
    (net (code "58") (name "unconnected-(ARDUINO_NANO1-D1{slash}TX-Pad16)") (class "Default")
      (node (ref "ARDUINO_NANO1") (pin "16") (pinfunction "D1/TX_16") (pintype "bidirectional"))
    )
    (net (code "59") (name "unconnected-(ARDUINO_NANO1-SCK{slash}D13-Pad1)") (class "Default")
      (node (ref "ARDUINO_NANO1") (pin "1") (pinfunction "SCK/D13_1") (pintype "bidirectional"))
    )
    (net (code "60") (name "unconnected-(ARDUINO_NANO1-~{RESET}-Pad13)") (class "Default")
      (node (ref "ARDUINO_NANO1") (pin "13") (pinfunction "~{RESET}_13") (pintype "input"))
    )
    (net (code "61") (name "unconnected-(ARDUINO_NANO1-~{RESET}-Pad18)") (class "Default")
      (node (ref "ARDUINO_NANO1") (pin "18") (pinfunction "~{RESET}_18") (pintype "input"))
    )
    (net (code "62") (name "unconnected-(J2-Pad6)") (class "Default")
      (node (ref "J2") (pin "6") (pinfunction "6_6") (pintype "passive"))
    )
    (net (code "63") (name "unconnected-(J3-Pad6)") (class "Default")
      (node (ref "J3") (pin "6") (pinfunction "6_6") (pintype "passive"))
    )
    (net (code "64") (name "unconnected-(J5-Pad6)") (class "Default")
      (node (ref "J5") (pin "6") (pinfunction "6_6") (pintype "passive"))
    )
    (net (code "65") (name "unconnected-(J7-Pad6)") (class "Default")
      (node (ref "J7") (pin "6") (pinfunction "6_6") (pintype "passive"))
    )
    (net (code "66") (name "unconnected-(J8-Pad6)") (class "Default")
      (node (ref "J8") (pin "6") (pinfunction "6_6") (pintype "passive"))
    )
    (net (code "67") (name "unconnected-(LED3-DO-Pad2-DOUT)") (class "Default")
      (node (ref "LED3") (pin "2-DOUT") (pinfunction "DO_2-DOUT") (pintype "output"))
    )
    (net (code "68") (name "unconnected-(U$23-2-PadP$2)") (class "Default")
      (node (ref "U$23") (pin "P$2") (pinfunction "2_P$2") (pintype "bidirectional"))
    )
  )
)
